# Sheet1.net
KiCad netlist of a schematic drawn in Altium Designer
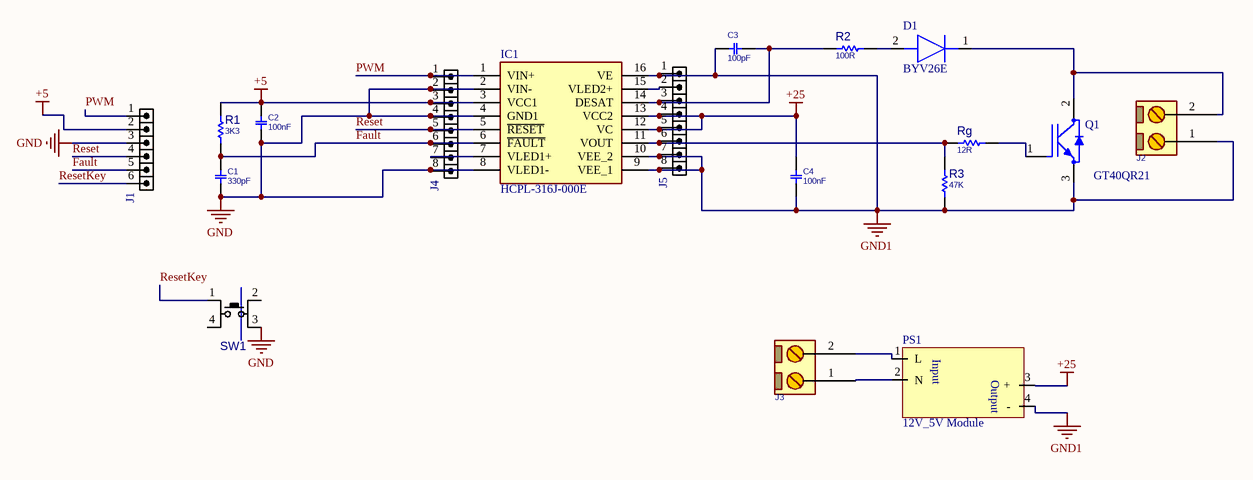
[diagram p0: Sheet1.SchDoc]

(export (version "E")
  (design (tool "Eeschema 10.0.6"))
  (components
    (comp (ref "C1")
      (value "330pF")
      (footprint "C_CER_D3")
      (description "CAP, THD, CER MULTI LAYER,")
      (fields (field (name "MANF_P#") "MANF_PART#") (field (name "MANF") "MANF"))
      (libsource (lib "CapCer_passive") (part "CAP_THD_CERML"))
    )
    (comp (ref "C2")
      (value "100nF")
      (footprint "C_CER_D6B")
      (description "CAP, THD, CER MULTI LAYER,")
      (fields (field (name "MANF_P#") "MANF_PART#") (field (name "MANF") "MANF"))
      (libsource (lib "CapCer_passive") (part "CAP_THD_CERML"))
    )
    (comp (ref "C3")
      (value "100pF")
      (footprint "C_CER_D3")
      (description "CAP, THD, CER MULTI LAYER,")
      (fields (field (name "MANF_P#") "MANF_PART#") (field (name "MANF") "MANF"))
      (libsource (lib "CapCer_passive") (part "CAP_THD_CERML"))
    )
    (comp (ref "C4")
      (value "100nF")
      (footprint "C_CER_D6B")
      (description "CAP, THD, CER MULTI LAYER,")
      (fields (field (name "MANF_P#") "MANF_PART#") (field (name "MANF") "MANF"))
      (libsource (lib "CapCer_passive") (part "CAP_THD_CERML"))
    )
    (comp (ref "D1")
      (value "BYV26E")
      (footprint "DIOAD1411W86L465D236")
      (description "Diode")
      (libsource (lib "SamacSys") (part "BYV26E"))
    )
    (comp (ref "IC1")
      (value "HCPL-316J-000E")
      (footprint "SamacSys:SOIC127P1016X391-16N")
      (description "Integrated Circuit")
      (fields (field (name "MOUSER PART NUMBER") "630-HCPL-316J-000E"))
      (libsource (lib "*") (part "HCPL-316J-000E"))
    )
    (comp (ref "J1")
      (value "HDR1X6")
      (footprint "HDR_M_1X6")
      (description "CONN, HEADER, Male, pitch: 2.54mm, 6POS")
      (libsource (lib "conn_header_2.54_st") (part "HDR_M_1X6"))
    )
    (comp (ref "J2")
      (value "CONN_TB2")
      (footprint "TBG_2")
      (description "CONN, TERMINAL BLOCK, 5.08mm pitch")
      (libsource (lib "conn_power_terminalB") (part "CONN_TB2"))
    )
    (comp (ref "J3")
      (value "CONN_TB2")
      (footprint "TBG_2")
      (description "CONN, TERMINAL BLOCK, 5.08mm pitch")
      (libsource (lib "conn_power_terminalB") (part "CONN_TB2"))
    )
    (comp (ref "J4")
      (value "HDR1X8")
      (footprint "HDR_M_1X8")
      (description "CONN, HEADER, Male, pitch: 2.54mm, 8POS")
      (libsource (lib "conn_header_2.54_st") (part "HDR_M_1X8"))
    )
    (comp (ref "J5")
      (value "HDR1X8")
      (footprint "HDR_M_1X8")
      (description "CONN, HEADER, Male, pitch: 2.54mm, 8POS")
      (libsource (lib "conn_header_2.54_st") (part "HDR_M_1X8"))
    )
    (comp (ref "PS1")
      (value "12V_5V Module")
      (footprint "12V_5V Module")
      (description "220V to 12V/15V Module")
      (libsource (lib "SidsLIB") (part "12V_5V Module"))
    )
    (comp (ref "Q1")
      (value "GT40QR21")
      (footprint "TO247_3")
      (description "IGBT")
      (fields (field (name "MF") "ON Semiconductor") (field (name "MP") "FGH40N60SFDTU"))
      (libsource (lib "SidsLIB") (part "IGBT"))
    )
    (comp (ref "R1")
      (value "3K3")
      (footprint "R025W_AX04")
      (description "RESISTOR, THD")
      (fields (field (name "MANF_P#") "RK73H1ETTP4701F") (field (name "MANF") "KOA SPEER"))
      (libsource (lib "passive_thd") (part "RES_THD"))
    )
    (comp (ref "R2")
      (value "100R")
      (footprint "R025W_AX04")
      (description "RESISTOR, THD")
      (fields (field (name "MANF_P#") "RK73H1ETTP4701F") (field (name "MANF") "KOA SPEER"))
      (libsource (lib "passive_thd") (part "RES_THD"))
    )
    (comp (ref "R3")
      (value "47K")
      (footprint "R025W_AX04")
      (description "RESISTOR, THD")
      (fields (field (name "MANF_P#") "RK73H1ETTP4701F") (field (name "MANF") "KOA SPEER"))
      (libsource (lib "passive_thd") (part "RES_THD"))
    )
    (comp (ref "Rg")
      (value "12R")
      (footprint "R2W_AX08")
      (description "RESISTOR, THD")
      (fields (field (name "MANF_P#") "RK73H1ETTP4701F") (field (name "MANF") "KOA SPEER"))
      (libsource (lib "passive_thd") (part "RES_THD"))
    )
    (comp (ref "SW1")
      (value "PUSHBUTTON")
      (footprint "SWPBT_SPDT_6X6X5")
      (description "SWITCH, PUSH BUTTON, TACTILE, THD, SPDT, 4X4MM")
      (libsource (lib "switch_tact_PUSHB") (part "SWPBT_SPDT_6X6X5"))
    )
  )
  (nets
    (net (code "1") (name "+5") (class "Default")
      (node (ref "C2") (pin "2") (pinfunction "2_2") (pintype "passive"))
      (node (ref "IC1") (pin "3") (pinfunction "VCC1_3") (pintype "passive"))
      (node (ref "J1") (pin "2") (pinfunction "2_2") (pintype "passive"))
      (node (ref "J4") (pin "3") (pinfunction "3_3") (pintype "passive"))
      (node (ref "R1") (pin "2") (pinfunction "2_2") (pintype "passive"))
    )
    (net (code "2") (name "+25") (class "Default")
      (node (ref "C4") (pin "2") (pinfunction "2_2") (pintype "passive"))
      (node (ref "IC1") (pin "12") (pinfunction "VC_12") (pintype "passive"))
      (node (ref "IC1") (pin "13") (pinfunction "VCC2_13") (pintype "passive"))
      (node (ref "J5") (pin "4") (pinfunction "4_4") (pintype "passive"))
      (node (ref "J5") (pin "5") (pinfunction "5_5") (pintype "passive"))
      (node (ref "PS1") (pin "3") (pinfunction "+_3") (pintype "passive"))
    )
    (net (code "3") (name "/Fault") (class "Default")
      (node (ref "C1") (pin "1") (pinfunction "1_1") (pintype "passive"))
      (node (ref "IC1") (pin "6") (pinfunction "~{FAULT}_6") (pintype "passive"))
      (node (ref "J1") (pin "5") (pinfunction "5_5") (pintype "passive"))
      (node (ref "J4") (pin "6") (pinfunction "6_6") (pintype "passive"))
      (node (ref "R1") (pin "1") (pinfunction "1_1") (pintype "passive"))
    )
    (net (code "4") (name "/PWM") (class "Default")
      (node (ref "IC1") (pin "1") (pinfunction "VIN+_1") (pintype "passive"))
      (node (ref "J1") (pin "1") (pinfunction "1_1") (pintype "passive"))
      (node (ref "J4") (pin "1") (pinfunction "1_1") (pintype "passive"))
    )
    (net (code "5") (name "/Reset") (class "Default")
      (node (ref "IC1") (pin "5") (pinfunction "~{RESET}_5") (pintype "passive"))
      (node (ref "J1") (pin "4") (pinfunction "4_4") (pintype "passive"))
      (node (ref "J4") (pin "5") (pinfunction "5_5") (pintype "passive"))
    )
    (net (code "6") (name "/ResetKey") (class "Default")
      (node (ref "J1") (pin "6") (pinfunction "6_6") (pintype "passive"))
      (node (ref "SW1") (pin "1") (pinfunction "P1_1") (pintype "passive"))
    )
    (net (code "7") (name "GND") (class "Default")
      (node (ref "C1") (pin "2") (pinfunction "2_2") (pintype "passive"))
      (node (ref "C2") (pin "1") (pinfunction "1_1") (pintype "passive"))
      (node (ref "IC1") (pin "2") (pinfunction "VIN-_2") (pintype "passive"))
      (node (ref "IC1") (pin "4") (pinfunction "GND1_4") (pintype "passive"))
      (node (ref "IC1") (pin "8") (pinfunction "VLED1-_8") (pintype "passive"))
      (node (ref "J1") (pin "3") (pinfunction "3_3") (pintype "passive"))
      (node (ref "J4") (pin "2") (pinfunction "2_2") (pintype "passive"))
      (node (ref "J4") (pin "4") (pinfunction "4_4") (pintype "passive"))
      (node (ref "J4") (pin "8") (pinfunction "8_8") (pintype "passive"))
      (node (ref "SW1") (pin "3") (pinfunction "P4_3") (pintype "passive"))
    )
    (net (code "8") (name "GND1") (class "Default")
      (node (ref "C3") (pin "1") (pinfunction "1_1") (pintype "passive"))
      (node (ref "C4") (pin "1") (pinfunction "1_1") (pintype "passive"))
      (node (ref "IC1") (pin "10") (pinfunction "VEE_2_10") (pintype "passive"))
      (node (ref "IC1") (pin "16") (pinfunction "VE_16") (pintype "passive"))
      (node (ref "IC1") (pin "9") (pinfunction "VEE_1_9") (pintype "passive"))
      (node (ref "J2") (pin "1") (pinfunction "1_1") (pintype "passive"))
      (node (ref "J5") (pin "1") (pinfunction "1_1") (pintype "passive"))
      (node (ref "J5") (pin "7") (pinfunction "7_7") (pintype "passive"))
      (node (ref "J5") (pin "8") (pinfunction "8_8") (pintype "passive"))
      (node (ref "PS1") (pin "4") (pinfunction "-_4") (pintype "passive"))
      (node (ref "Q1") (pin "3") (pinfunction "E_3") (pintype "passive"))
      (node (ref "R3") (pin "1") (pinfunction "1_1") (pintype "passive"))
    )
    (net (code "9") (name "Net-(D1-A)") (class "Default")
      (node (ref "D1") (pin "2") (pinfunction "A_2") (pintype "passive"))
      (node (ref "R2") (pin "2") (pinfunction "2_2") (pintype "passive"))
    )
    (net (code "10") (name "Net-(D1-K)") (class "Default")
      (node (ref "D1") (pin "1") (pinfunction "K_1") (pintype "passive"))
      (node (ref "J2") (pin "2") (pinfunction "2_2") (pintype "passive"))
      (node (ref "Q1") (pin "2") (pinfunction "C_2") (pintype "passive"))
    )
    (net (code "11") (name "Net-(IC1-DESAT)") (class "Default")
      (node (ref "C3") (pin "2") (pinfunction "2_2") (pintype "passive"))
      (node (ref "IC1") (pin "14") (pinfunction "DESAT_14") (pintype "passive"))
      (node (ref "J5") (pin "3") (pinfunction "3_3") (pintype "passive"))
      (node (ref "R2") (pin "1") (pinfunction "1_1") (pintype "passive"))
    )
    (net (code "12") (name "Net-(IC1-VLED1+)") (class "Default")
      (node (ref "IC1") (pin "7") (pinfunction "VLED1+_7") (pintype "passive"))
      (node (ref "J4") (pin "7") (pinfunction "7_7") (pintype "passive"))
    )
    (net (code "13") (name "Net-(IC1-VLED2+)") (class "Default")
      (node (ref "IC1") (pin "15") (pinfunction "VLED2+_15") (pintype "passive"))
      (node (ref "J5") (pin "2") (pinfunction "2_2") (pintype "passive"))
    )
    (net (code "14") (name "Net-(IC1-VOUT)") (class "Default")
      (node (ref "IC1") (pin "11") (pinfunction "VOUT_11") (pintype "passive"))
      (node (ref "J5") (pin "6") (pinfunction "6_6") (pintype "passive"))
      (node (ref "R3") (pin "2") (pinfunction "2_2") (pintype "passive"))
      (node (ref "Rg") (pin "1") (pinfunction "1_1") (pintype "passive"))
    )
    (net (code "15") (name "Net-(PS1-L)") (class "Default")
      (node (ref "J3") (pin "2") (pinfunction "2_2") (pintype "passive"))
      (node (ref "PS1") (pin "1") (pinfunction "L_1") (pintype "passive"))
    )
    (net (code "16") (name "Net-(PS1-N)") (class "Default")
      (node (ref "J3") (pin "1") (pinfunction "1_1") (pintype "passive"))
      (node (ref "PS1") (pin "2") (pinfunction "N_2") (pintype "passive"))
    )
    (net (code "17") (name "Net-(Q1-G)") (class "Default")
      (node (ref "Q1") (pin "1") (pinfunction "G_1") (pintype "passive"))
      (node (ref "Rg") (pin "2") (pinfunction "2_2") (pintype "passive"))
    )
    (net (code "18") (name "unconnected-(SW1-P2-Pad4)") (class "Default")
      (node (ref "SW1") (pin "4") (pinfunction "P2_4") (pintype "passive"))
    )
    (net (code "19") (name "unconnected-(SW1-P3-Pad2)") (class "Default")
      (node (ref "SW1") (pin "2") (pinfunction "P3_2") (pintype "passive"))
    )
  )
)
